# Simple_2in2_flex.net
KiCad netlist of a schematic drawn in EAGLE
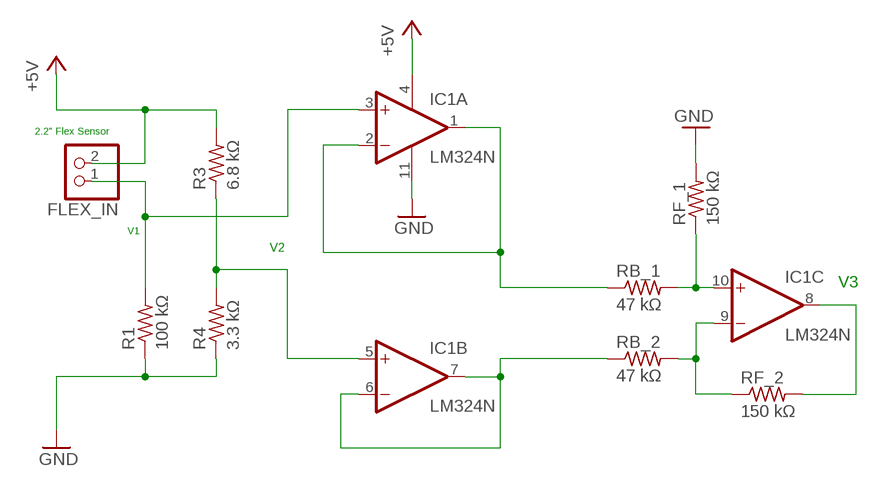
[diagram p0: schematic, sheet 1]

(export (version "E")
  (design (tool "Eeschema 10.0.6"))
  (components
    (comp (ref "FLEX_IN")
      (value "PINHD-1X2")
      (footprint "eagle-import:1X02")
      (libsource (lib "eagle-import") (part "PINHD-1X2"))
    )
    (comp (ref "IC1")
      (value "LM324N")
      (footprint "eagle-import:DIL14")
      (libsource (lib "eagle-import") (part "LM324N"))
    )
    (comp (ref "R1")
      (value "100 kΩ")
      (footprint "eagle-import:0204_5")
      (libsource (lib "eagle-import") (part "R-US_0204/5"))
    )
    (comp (ref "R3")
      (value "6.8 kΩ")
      (footprint "eagle-import:0204_5")
      (libsource (lib "eagle-import") (part "R-US_0204/5"))
    )
    (comp (ref "R4")
      (value "3.3 kΩ")
      (footprint "eagle-import:0204_5")
      (libsource (lib "eagle-import") (part "R-US_0204/5"))
    )
    (comp (ref "RB_1")
      (value "47 kΩ")
      (footprint "eagle-import:0204_5")
      (libsource (lib "eagle-import") (part "resistor_348_R-US_0204/5"))
    )
    (comp (ref "RB_2")
      (value "47 kΩ")
      (footprint "eagle-import:0204_5")
      (libsource (lib "eagle-import") (part "resistor_348_R-US_0204/5"))
    )
    (comp (ref "RF_1")
      (value "150 kΩ")
      (footprint "eagle-import:0204_5")
      (libsource (lib "eagle-import") (part "resistor_348_R-US_0204/5"))
    )
    (comp (ref "RF_2")
      (value "150 kΩ")
      (footprint "eagle-import:0204_5")
      (libsource (lib "eagle-import") (part "resistor_348_R-US_0204/5"))
    )
  )
  (nets
    (net (code "1") (name "+5V") (class "Default")
      (node (ref "FLEX_IN") (pin "2") (pinfunction "2_2") (pintype "passive"))
      (node (ref "IC1") (pin "4") (pinfunction "V+_4") (pintype "power_in"))
      (node (ref "R3") (pin "2") (pinfunction "2_2") (pintype "passive"))
    )
    (net (code "2") (name "GND") (class "Default")
      (node (ref "IC1") (pin "11") (pinfunction "V-_11") (pintype "power_in"))
      (node (ref "R1") (pin "1") (pinfunction "1_1") (pintype "passive"))
      (node (ref "R4") (pin "1") (pinfunction "1_1") (pintype "passive"))
      (node (ref "RF_1") (pin "2") (pinfunction "2_2") (pintype "passive"))
    )
    (net (code "3") (name "Net-(IC1A-+IN)") (class "Default")
      (node (ref "FLEX_IN") (pin "1") (pinfunction "1_1") (pintype "passive"))
      (node (ref "IC1") (pin "3") (pinfunction "+IN_3") (pintype "input"))
      (node (ref "R1") (pin "2") (pinfunction "2_2") (pintype "passive"))
    )
    (net (code "4") (name "Net-(IC1A--IN)") (class "Default")
      (node (ref "IC1") (pin "1") (pinfunction "OUT_1") (pintype "output"))
      (node (ref "IC1") (pin "2") (pinfunction "-IN_2") (pintype "input"))
      (node (ref "RB_1") (pin "1") (pinfunction "1_1") (pintype "passive"))
    )
    (net (code "5") (name "Net-(IC1B-+IN)") (class "Default")
      (node (ref "IC1") (pin "5") (pinfunction "+IN_5") (pintype "input"))
      (node (ref "R3") (pin "1") (pinfunction "1_1") (pintype "passive"))
      (node (ref "R4") (pin "2") (pinfunction "2_2") (pintype "passive"))
    )
    (net (code "6") (name "Net-(IC1B--IN)") (class "Default")
      (node (ref "IC1") (pin "6") (pinfunction "-IN_6") (pintype "input"))
      (node (ref "IC1") (pin "7") (pinfunction "OUT_7") (pintype "output"))
      (node (ref "RB_2") (pin "1") (pinfunction "1_1") (pintype "passive"))
    )
    (net (code "7") (name "Net-(IC1C-+IN)") (class "Default")
      (node (ref "IC1") (pin "10") (pinfunction "+IN_10") (pintype "input"))
      (node (ref "RB_1") (pin "2") (pinfunction "2_2") (pintype "passive"))
      (node (ref "RF_1") (pin "1") (pinfunction "1_1") (pintype "passive"))
    )
    (net (code "8") (name "Net-(IC1C--IN)") (class "Default")
      (node (ref "IC1") (pin "9") (pinfunction "-IN_9") (pintype "input"))
      (node (ref "RB_2") (pin "2") (pinfunction "2_2") (pintype "passive"))
      (node (ref "RF_2") (pin "1") (pinfunction "1_1") (pintype "passive"))
    )
    (net (code "9") (name "Net-(IC1C-OUT)") (class "Default")
      (node (ref "IC1") (pin "8") (pinfunction "OUT_8") (pintype "output"))
      (node (ref "RF_2") (pin "2") (pinfunction "2_2") (pintype "passive"))
    )
  )
)
